# SH_SFW2_V1_0.net
KiCad netlist of a schematic drawn in Altium Designer
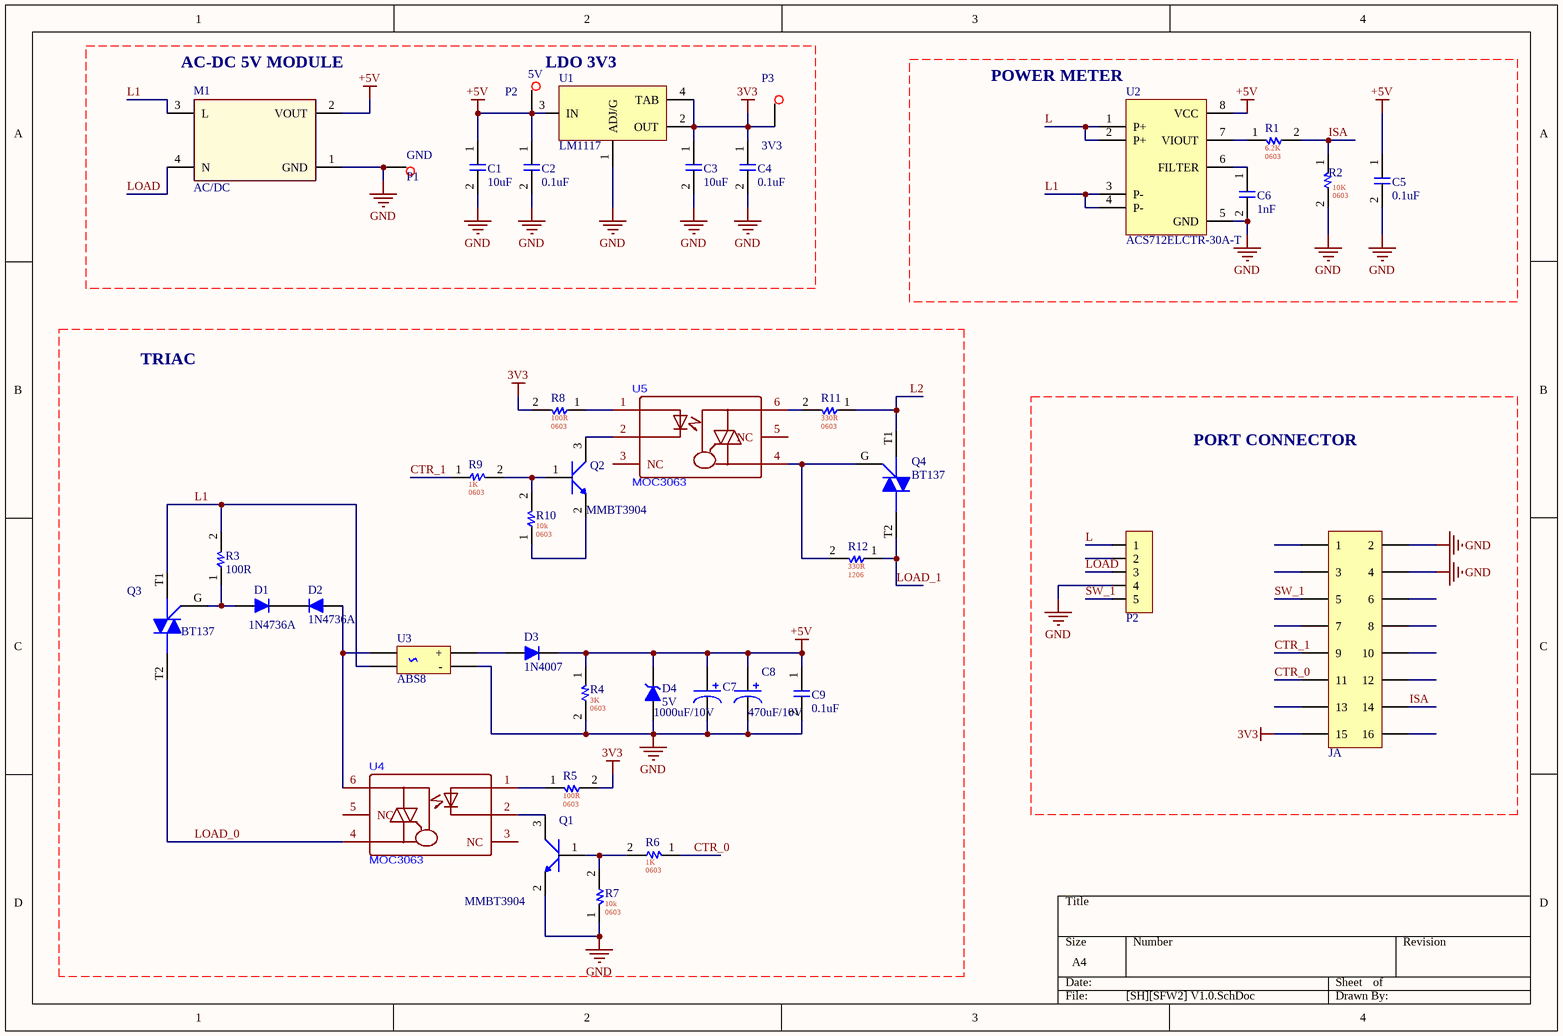
[diagram p0: [SH][SFW2] V1.0.SchDoc]

(export (version "E")
  (design (tool "Eeschema 10.0.6"))
  (components
    (comp (ref "3V3") (value "P3") (footprint "TEXT_POINT") (libsource (lib "Kienlib") (part "P1")))
    (comp (ref "5V") (value "P2") (footprint "TEXT_POINT") (libsource (lib "Kienlib") (part "P1")))
    (comp (ref "C1")
      (value "10uF")
      (footprint "0805 C")
      (description "0603 10 uF 10 V ±10% Tolerance X5R Multilayer Ceramic Chip Capacitor")
      (libsource (lib "Kienlib") (part "CAP NOP"))
    )
    (comp (ref "C2")
      (value "0.1uF")
      (footprint "0603 C")
      (description "Cap Ceramic 0.1uF 10V X7R 10% SMD 0603 125°C Paper T/R")
      (libsource (lib "Kienlib") (part "CAP NOP"))
    )
    (comp (ref "C3")
      (value "10uF")
      (footprint "0805 C")
      (description "0603 10 uF 10 V ±10% Tolerance X5R Multilayer Ceramic Chip Capacitor")
      (libsource (lib "Kienlib") (part "CAP NOP"))
    )
    (comp (ref "C4")
      (value "0.1uF")
      (footprint "0603 C")
      (description "Cap Ceramic 0.1uF 10V X7R 10% SMD 0603 125°C Paper T/R")
      (libsource (lib "Kienlib") (part "CAP NOP"))
    )
    (comp (ref "C5")
      (value "0.1uF")
      (footprint "0603 C")
      (description "Cap Ceramic 0.1uF 10V X7R 10% SMD 0603 125°C Paper T/R")
      (libsource (lib "Kienlib") (part "CAP NOP"))
    )
    (comp (ref "C6")
      (value "1nF")
      (footprint "0603 C")
      (description "CAP CER 0603 1NF 10V ULTRA STABL")
      (libsource (lib "Kienlib") (part "CAP NOP"))
    )
    (comp (ref "C7")
      (value "1000uF/10V")
      (footprint "CAPAP 8X11.5 P3.5")
      (description "Cap Aluminum Lytic 1000uF 10V 20% (10 X 16mm) Radial 5mm 1790mA 4000h 105C Ammo")
      (libsource (lib "Kienlib") (part "CAP POLAR"))
    )
    (comp (ref "C8")
      (value "470uF/10V")
      (footprint "CAPAE 5X9 P2 ORANGE")
      (description "Cap Aluminum 470uF 10V 20% (8 X 11.5mm) Radial 5mm 950mA 3000h 105C Ammo Pack")
      (libsource (lib "Kienlib") (part "CAP POLAR"))
    )
    (comp (ref "C9")
      (value "0.1uF")
      (footprint "0603 C")
      (description "Cap Ceramic 0.1uF 10V X7R 10% SMD 0603 125°C Paper T/R")
      (libsource (lib "Kienlib") (part "CAP NOP"))
    )
    (comp (ref "D1")
      (value "1N4736A")
      (footprint "DO214AC")
      (description "1N4736 Series 1 W 6.8 V 10 uA Axial Through Hole Zener Diode - DO-41")
      (libsource (lib "Kienlib") (part "Diode schottky"))
    )
    (comp (ref "D2")
      (value "1N4736A")
      (footprint "DO214AC")
      (description "1N4736 Series 1 W 6.8 V 10 uA Axial Through Hole Zener Diode - DO-41")
      (libsource (lib "Kienlib") (part "Diode schottky"))
    )
    (comp (ref "D3")
      (value "1N4007")
      (footprint "SOD-323")
      (description "Diode Standard 1000V 1A Through Hole DO-204AL (DO-41)")
      (libsource (lib "Kienlib") (part "Diode schottky"))
    )
    (comp (ref "D4")
      (value "5V")
      (footprint "SOD-80C")
      (description "Diode Zener 5V 1W")
      (fields (field (name "EDITOR") "MMUOP"))
      (libsource (lib "Kienlib") (part "Diode Zener"))
    )
    (comp (ref "GND") (value "P1") (footprint "TEXT_POINT") (libsource (lib "Kienlib") (part "P1")))
    (comp (ref "JA")
      (value "rao doi")
      (footprint "T")
      (description "Hàng Rào Cái Đôi 2.54mm 16Chân 2 Hàng SMD\r\nFemale Header 2.54mm 16 Way 2 Row SMD")
      (libsource (lib "Kienlib") (part "P2x8"))
    )
    (comp (ref "M1")
      (value "AC/DC")
      (footprint "AC-DC 5V K4H24")
      (description "AC-DC 5V 700mA 3.5W Power Supply Buck Converter Step Down Module 220V To 5V")
      (libsource (lib "Kienlib") (part "AC/DC"))
    )
    (comp (ref "P2") (value "P5") (footprint "TBL004V") (libsource (lib "Kienlib") (part "P5")))
    (comp (ref "Q1")
      (value "MMBT3904")
      (footprint "SOT 23-3")
      (description "Bipolar (BJT) Transistor NPN 40 V 200 mA 300MHz 350 mW Surface Mount SOT-23-3 (TO-236)")
      (libsource (lib "Kienlib") (part "TRANS NPN"))
    )
    (comp (ref "Q2")
      (value "MMBT3904")
      (footprint "SOT 23-3")
      (description "Bipolar (BJT) Transistor NPN 40 V 200 mA 300MHz 350 mW Surface Mount SOT-23-3 (TO-236)")
      (libsource (lib "Kienlib") (part "TRANS NPN"))
    )
    (comp (ref "Q3")
      (value "BT137")
      (footprint "TO_252")
      (description "TRIAC Standard 600 V 8 A Surface Mount D2PAK")
      (libsource (lib "Kienlib") (part "TRIAC"))
    )
    (comp (ref "Q4")
      (value "BT137")
      (footprint "TO_252")
      (description "TRIAC Standard 600 V 8 A Surface Mount D2PAK")
      (libsource (lib "Kienlib") (part "TRIAC"))
    )
    (comp (ref "R1")
      (value "6.2K")
      (footprint "0603 R")
      (description "6.2KΩ 1% 0603 SMD")
      (fields (field (name "FP") "0603") (field (name "Comment") "3K") (field (name "CREATOR") "MMUOP"))
      (libsource (lib "Res") (part "0603 10k 1%"))
    )
    (comp (ref "R2")
      (value "10K")
      (footprint "0603 R")
      (description "10KΩ 1% 0603 SMD")
      (fields (field (name "FP") "0603") (field (name "Comment") "3K") (field (name "CREATOR") "MMUOP"))
      (libsource (lib "Res") (part "0603 10k 1%"))
    )
    (comp (ref "R3")
      (value "100R")
      (footprint "0805 R")
      (description "100KΩ 1% 0805 SMD")
      (libsource (lib "Kienlib") (part "Res SMD"))
    )
    (comp (ref "R4")
      (value "3K")
      (footprint "0603 R")
      (description "3KΩ 0603 SMD")
      (fields (field (name "FP") "0603") (field (name "CREATOR") "MMUOP"))
      (libsource (lib "Res") (part "0603 10k 1%"))
    )
    (comp (ref "R5")
      (value "100R")
      (footprint "0603 R")
      (description "100R 1% 0603 SMD")
      (fields (field (name "FP") "0603") (field (name "CREATOR") "MMUOP"))
      (libsource (lib "Res") (part "0603 10k 1%"))
    )
    (comp (ref "R6")
      (value "1K")
      (footprint "0603 R")
      (description "1KΩ 1% 0603 SMD")
      (fields (field (name "FP") "0603") (field (name "CREATOR") "MMUOP"))
      (libsource (lib "Res") (part "0603 10k 1%"))
    )
    (comp (ref "R7")
      (value "10k")
      (footprint "0603 R")
      (description "10KΩ 1% 0603 SMD")
      (fields (field (name "FP") "0603") (field (name "CREATOR") "MMUOP"))
      (libsource (lib "Res") (part "0603 10k 1%"))
    )
    (comp (ref "R8")
      (value "100R")
      (footprint "0603 R")
      (description "100R 1% 0603 SMD")
      (fields (field (name "FP") "0603") (field (name "CREATOR") "MMUOP"))
      (libsource (lib "Res") (part "0603 10k 1%"))
    )
    (comp (ref "R9")
      (value "1K")
      (footprint "0603 R")
      (description "1KΩ 1% 0603 SMD")
      (fields (field (name "FP") "0603") (field (name "CREATOR") "MMUOP"))
      (libsource (lib "Res") (part "0603 10k 1%"))
    )
    (comp (ref "R10")
      (value "10k")
      (footprint "0603 R")
      (description "10KΩ 1% 0603 SMD")
      (fields (field (name "FP") "0603") (field (name "CREATOR") "MMUOP"))
      (libsource (lib "Res") (part "0603 10k 1%"))
    )
    (comp (ref "R11")
      (value "330R")
      (footprint "0603 R")
      (description "100R 1% 0603 SMD")
      (fields (field (name "FP") "0603") (field (name "Comment") "100R") (field (name "CREATOR") "MMUOP"))
      (libsource (lib "Res") (part "0603 10k 1%"))
    )
    (comp (ref "R12")
      (value "330R")
      (footprint "0603 R")
      (description "100R 1% 0603 SMD")
      (fields (field (name "FP") "1206") (field (name "Comment") "100R") (field (name "CREATOR") "MMUOP"))
      (libsource (lib "Res") (part "0603 10k 1%"))
    )
    (comp (ref "U1")
      (value "LM1117")
      (footprint "SOT23-4")
      (description "800-mA 15-V linear voltage regulator 4-SOT-223")
      (libsource (lib "Kienlib") (part "LM1117"))
    )
    (comp (ref "U2")
      (value "ACS712ELCTR-30A-T")
      (footprint "SOIC 8")
      (description "Current Sensor 30A 1 Channel Hall Effect, Open Loop Bidirectional 8-SOIC (0.154\", 3.90mm Width)")
      (libsource (lib "Kienlib") (part "ACS71240"))
    )
    (comp (ref "U3")
      (value "ABS8")
      (footprint "4PIN SOP")
      (description "Bridge Rectifier Single Phase Standard 800V Surface Mount ABS")
      (libsource (lib "Kienlib") (part "DIODE BRIGH"))
    )
    (comp (ref "U4")
      (value "MOC3063")
      (footprint "TO252")
      (description "Optoisolator Triac Output 4170Vrms 1 Channel 6-SMD")
      (libsource (lib "altium-import") (part "root_0_mirrored_CYMOC3063_"))
    )
    (comp (ref "U5")
      (value "MOC3063")
      (footprint "TO252")
      (description "Optoisolator Triac Output 4170Vrms 1 Channel 6-SMD")
      (libsource (lib "altium-import") (part "root_0_CYMOC3063_"))
    )
  )
  (nets
    (net (code "1") (name "+5V") (class "Default")
      (node (ref "5V") (pin "1") (pinfunction "P_1") (pintype "passive"))
      (node (ref "C1") (pin "1") (pinfunction "1_1") (pintype "passive"))
      (node (ref "C2") (pin "1") (pinfunction "1_1") (pintype "passive"))
      (node (ref "C5") (pin "1") (pinfunction "1_1") (pintype "passive"))
      (node (ref "C7") (pin "1") (pinfunction "1_1") (pintype "passive"))
      (node (ref "C8") (pin "1") (pinfunction "1_1") (pintype "passive"))
      (node (ref "C9") (pin "1") (pinfunction "1_1") (pintype "passive"))
      (node (ref "D3") (pin "2") (pinfunction "2_2") (pintype "passive"))
      (node (ref "D4") (pin "2") (pinfunction "2_2") (pintype "passive"))
      (node (ref "M1") (pin "2") (pinfunction "VOUT_2") (pintype "passive"))
      (node (ref "R4") (pin "1") (pinfunction "1_1") (pintype "passive"))
      (node (ref "U1") (pin "3") (pinfunction "IN_3") (pintype "passive"))
      (node (ref "U2") (pin "8") (pinfunction "VCC_8") (pintype "passive"))
    )
    (net (code "2") (name "/CTR_0") (class "Default")
      (node (ref "JA") (pin "11") (pinfunction "11_11") (pintype "passive"))
      (node (ref "R6") (pin "1") (pinfunction "1_1") (pintype "passive"))
    )
    (net (code "3") (name "/CTR_1") (class "Default")
      (node (ref "JA") (pin "9") (pinfunction "9_9") (pintype "passive"))
      (node (ref "R9") (pin "1") (pinfunction "1_1") (pintype "passive"))
    )
    (net (code "4") (name "/ISA") (class "Default")
      (node (ref "JA") (pin "14") (pinfunction "14_14") (pintype "passive"))
      (node (ref "R1") (pin "2") (pinfunction "2_2") (pintype "passive"))
      (node (ref "R2") (pin "1") (pinfunction "1_1") (pintype "passive"))
    )
    (net (code "5") (name "/L") (class "Default")
      (node (ref "P2") (pin "1") (pinfunction "1_1") (pintype "passive"))
      (node (ref "U2") (pin "1") (pinfunction "P+_1") (pintype "passive"))
      (node (ref "U2") (pin "2") (pinfunction "P+_2") (pintype "passive"))
    )
    (net (code "6") (name "/L1") (class "Default")
      (node (ref "M1") (pin "3") (pinfunction "L_3") (pintype "passive"))
      (node (ref "Q3") (pin "T1") (pinfunction "T1_T1") (pintype "passive"))
      (node (ref "R3") (pin "2") (pinfunction "2_2") (pintype "passive"))
      (node (ref "U2") (pin "3") (pinfunction "P-_3") (pintype "passive"))
      (node (ref "U2") (pin "4") (pinfunction "P-_4") (pintype "passive"))
      (node (ref "U3") (pin "4") (pinfunction "4_4") (pintype "passive"))
    )
    (net (code "7") (name "/L2") (class "Default")
      (node (ref "Q4") (pin "T1") (pinfunction "T1_T1") (pintype "passive"))
      (node (ref "R11") (pin "1") (pinfunction "1_1") (pintype "passive"))
    )
    (net (code "8") (name "/LOAD") (class "Default")
      (node (ref "M1") (pin "4") (pinfunction "N_4") (pintype "passive"))
      (node (ref "P2") (pin "3") (pinfunction "3_3") (pintype "passive"))
    )
    (net (code "9") (name "/LOAD_0") (class "Default")
      (node (ref "Q3") (pin "T2") (pinfunction "T2_T2") (pintype "passive"))
      (node (ref "U4") (pin "4") (pinfunction "MT_4") (pintype "passive"))
    )
    (net (code "10") (name "/LOAD_1") (class "Default")
      (node (ref "Q4") (pin "T2") (pinfunction "T2_T2") (pintype "passive"))
      (node (ref "R12") (pin "1") (pinfunction "1_1") (pintype "passive"))
    )
    (net (code "11") (name "/SW_1") (class "Default")
      (node (ref "JA") (pin "5") (pinfunction "5_5") (pintype "passive"))
      (node (ref "P2") (pin "5") (pinfunction "5_5") (pintype "passive"))
    )
    (net (code "12") (name "3V3") (class "Default")
      (node (ref "3V3") (pin "1") (pinfunction "P_1") (pintype "passive"))
      (node (ref "C3") (pin "1") (pinfunction "1_1") (pintype "passive"))
      (node (ref "C4") (pin "1") (pinfunction "1_1") (pintype "passive"))
      (node (ref "JA") (pin "15") (pinfunction "15_15") (pintype "passive"))
      (node (ref "R5") (pin "2") (pinfunction "2_2") (pintype "passive"))
      (node (ref "R8") (pin "2") (pinfunction "2_2") (pintype "passive"))
      (node (ref "U1") (pin "2") (pinfunction "OUT_2") (pintype "passive"))
      (node (ref "U1") (pin "4") (pinfunction "TAB_4") (pintype "passive"))
    )
    (net (code "13") (name "GND") (class "Default")
      (node (ref "C1") (pin "2") (pinfunction "2_2") (pintype "passive"))
      (node (ref "C2") (pin "2") (pinfunction "2_2") (pintype "passive"))
      (node (ref "C3") (pin "2") (pinfunction "2_2") (pintype "passive"))
      (node (ref "C4") (pin "2") (pinfunction "2_2") (pintype "passive"))
      (node (ref "C5") (pin "2") (pinfunction "2_2") (pintype "passive"))
      (node (ref "C6") (pin "2") (pinfunction "2_2") (pintype "passive"))
      (node (ref "C7") (pin "2") (pinfunction "2_2") (pintype "passive"))
      (node (ref "C8") (pin "2") (pinfunction "2_2") (pintype "passive"))
      (node (ref "C9") (pin "2") (pinfunction "2_2") (pintype "passive"))
      (node (ref "D4") (pin "1") (pinfunction "1_1") (pintype "passive"))
      (node (ref "GND") (pin "1") (pinfunction "P_1") (pintype "passive"))
      (node (ref "JA") (pin "2") (pinfunction "2_2") (pintype "passive"))
      (node (ref "JA") (pin "4") (pinfunction "4_4") (pintype "passive"))
      (node (ref "M1") (pin "1") (pinfunction "GND_1") (pintype "passive"))
      (node (ref "P2") (pin "4") (pinfunction "4_4") (pintype "passive"))
      (node (ref "Q1") (pin "2") (pinfunction "E_2") (pintype "passive"))
      (node (ref "R2") (pin "2") (pinfunction "2_2") (pintype "passive"))
      (node (ref "R4") (pin "2") (pinfunction "2_2") (pintype "passive"))
      (node (ref "R7") (pin "1") (pinfunction "1_1") (pintype "passive"))
      (node (ref "U1") (pin "1") (pinfunction "ADJ/G_1") (pintype "passive"))
      (node (ref "U2") (pin "5") (pinfunction "GND_5") (pintype "passive"))
      (node (ref "U3") (pin "2") (pinfunction "-_2") (pintype "passive"))
    )
    (net (code "14") (name "Net-(D1-Pad1)") (class "Default")
      (node (ref "D1") (pin "1") (pinfunction "1_1") (pintype "passive"))
      (node (ref "Q3") (pin "G") (pinfunction "G_G") (pintype "passive"))
      (node (ref "R3") (pin "1") (pinfunction "1_1") (pintype "passive"))
    )
    (net (code "15") (name "Net-(D1-Pad2)") (class "Default")
      (node (ref "D1") (pin "2") (pinfunction "2_2") (pintype "passive"))
      (node (ref "D2") (pin "2") (pinfunction "2_2") (pintype "passive"))
    )
    (net (code "16") (name "Net-(D2-Pad1)") (class "Default")
      (node (ref "D2") (pin "1") (pinfunction "1_1") (pintype "passive"))
      (node (ref "U3") (pin "3") (pinfunction "3_3") (pintype "passive"))
      (node (ref "U4") (pin "6") (pinfunction "MT_6") (pintype "passive"))
    )
    (net (code "17") (name "Net-(Q1-B)") (class "Default")
      (node (ref "Q1") (pin "1") (pinfunction "B_1") (pintype "passive"))
      (node (ref "R6") (pin "2") (pinfunction "2_2") (pintype "passive"))
      (node (ref "R7") (pin "2") (pinfunction "2_2") (pintype "passive"))
    )
    (net (code "18") (name "Net-(Q1-C)") (class "Default")
      (node (ref "Q1") (pin "3") (pinfunction "C_3") (pintype "passive"))
      (node (ref "U4") (pin "2") (pinfunction "CAT_2") (pintype "passive"))
    )
    (net (code "19") (name "Net-(Q2-B)") (class "Default")
      (node (ref "Q2") (pin "1") (pinfunction "B_1") (pintype "passive"))
      (node (ref "R10") (pin "2") (pinfunction "2_2") (pintype "passive"))
      (node (ref "R9") (pin "2") (pinfunction "2_2") (pintype "passive"))
    )
    (net (code "20") (name "Net-(Q2-C)") (class "Default")
      (node (ref "Q2") (pin "3") (pinfunction "C_3") (pintype "passive"))
      (node (ref "U5") (pin "2") (pinfunction "CAT_2") (pintype "passive"))
    )
    (net (code "21") (name "Net-(Q2-E)") (class "Default")
      (node (ref "Q2") (pin "2") (pinfunction "E_2") (pintype "passive"))
      (node (ref "R10") (pin "1") (pinfunction "1_1") (pintype "passive"))
    )
    (net (code "22") (name "Net-(Q4-PadG)") (class "Default")
      (node (ref "Q4") (pin "G") (pinfunction "G_G") (pintype "passive"))
      (node (ref "R12") (pin "2") (pinfunction "2_2") (pintype "passive"))
      (node (ref "U5") (pin "4") (pinfunction "MT_4") (pintype "passive"))
    )
    (net (code "23") (name "Net-(R11-Pad2)") (class "Default")
      (node (ref "R11") (pin "2") (pinfunction "2_2") (pintype "passive"))
      (node (ref "U5") (pin "6") (pinfunction "MT_6") (pintype "passive"))
    )
    (net (code "24") (name "Net-(U2-FILTER)") (class "Default")
      (node (ref "C6") (pin "1") (pinfunction "1_1") (pintype "passive"))
      (node (ref "U2") (pin "6") (pinfunction "FILTER_6") (pintype "passive"))
    )
    (net (code "25") (name "Net-(U2-VIOUT)") (class "Default")
      (node (ref "R1") (pin "1") (pinfunction "1_1") (pintype "passive"))
      (node (ref "U2") (pin "7") (pinfunction "VIOUT_7") (pintype "passive"))
    )
    (net (code "26") (name "Net-(U3-+)") (class "Default")
      (node (ref "D3") (pin "1") (pinfunction "1_1") (pintype "passive"))
      (node (ref "U3") (pin "1") (pinfunction "+_1") (pintype "passive"))
    )
    (net (code "27") (name "Net-(U4-AN)") (class "Default")
      (node (ref "R5") (pin "1") (pinfunction "1_1") (pintype "passive"))
      (node (ref "U4") (pin "1") (pinfunction "AN_1") (pintype "passive"))
    )
    (net (code "28") (name "Net-(U5-AN)") (class "Default")
      (node (ref "R8") (pin "1") (pinfunction "1_1") (pintype "passive"))
      (node (ref "U5") (pin "1") (pinfunction "AN_1") (pintype "passive"))
    )
    (net (code "29") (name "unconnected-(JA-Pad1)") (class "Default")
      (node (ref "JA") (pin "1") (pinfunction "1_1") (pintype "passive"))
    )
    (net (code "30") (name "unconnected-(JA-Pad3)") (class "Default")
      (node (ref "JA") (pin "3") (pinfunction "3_3") (pintype "passive"))
    )
    (net (code "31") (name "unconnected-(JA-Pad6)") (class "Default")
      (node (ref "JA") (pin "6") (pinfunction "6_6") (pintype "passive"))
    )
    (net (code "32") (name "unconnected-(JA-Pad7)") (class "Default")
      (node (ref "JA") (pin "7") (pinfunction "7_7") (pintype "passive"))
    )
    (net (code "33") (name "unconnected-(JA-Pad8)") (class "Default")
      (node (ref "JA") (pin "8") (pinfunction "8_8") (pintype "passive"))
    )
    (net (code "34") (name "unconnected-(JA-Pad10)") (class "Default")
      (node (ref "JA") (pin "10") (pinfunction "10_10") (pintype "passive"))
    )
    (net (code "35") (name "unconnected-(JA-Pad12)") (class "Default")
      (node (ref "JA") (pin "12") (pinfunction "12_12") (pintype "passive"))
    )
    (net (code "36") (name "unconnected-(JA-Pad13)") (class "Default")
      (node (ref "JA") (pin "13") (pinfunction "13_13") (pintype "passive"))
    )
    (net (code "37") (name "unconnected-(JA-Pad16)") (class "Default")
      (node (ref "JA") (pin "16") (pinfunction "16_16") (pintype "passive"))
    )
    (net (code "38") (name "unconnected-(P2-Pad2)") (class "Default")
      (node (ref "P2") (pin "2") (pinfunction "2_2") (pintype "passive"))
    )
    (net (code "39") (name "unconnected-(U4-NC-Pad3)") (class "Default")
      (node (ref "U4") (pin "3") (pinfunction "NC_3") (pintype "passive"))
    )
    (net (code "40") (name "unconnected-(U4-NC-Pad5)") (class "Default")
      (node (ref "U4") (pin "5") (pinfunction "NC_5") (pintype "passive"))
    )
    (net (code "41") (name "unconnected-(U5-NC-Pad3)") (class "Default")
      (node (ref "U5") (pin "3") (pinfunction "NC_3") (pintype "passive"))
    )
    (net (code "42") (name "unconnected-(U5-NC-Pad5)") (class "Default")
      (node (ref "U5") (pin "5") (pinfunction "NC_5") (pintype "passive"))
    )
  )
)
